# Thing_Plus_ESP32_C6.net
KiCad netlist of a schematic drawn in EAGLE
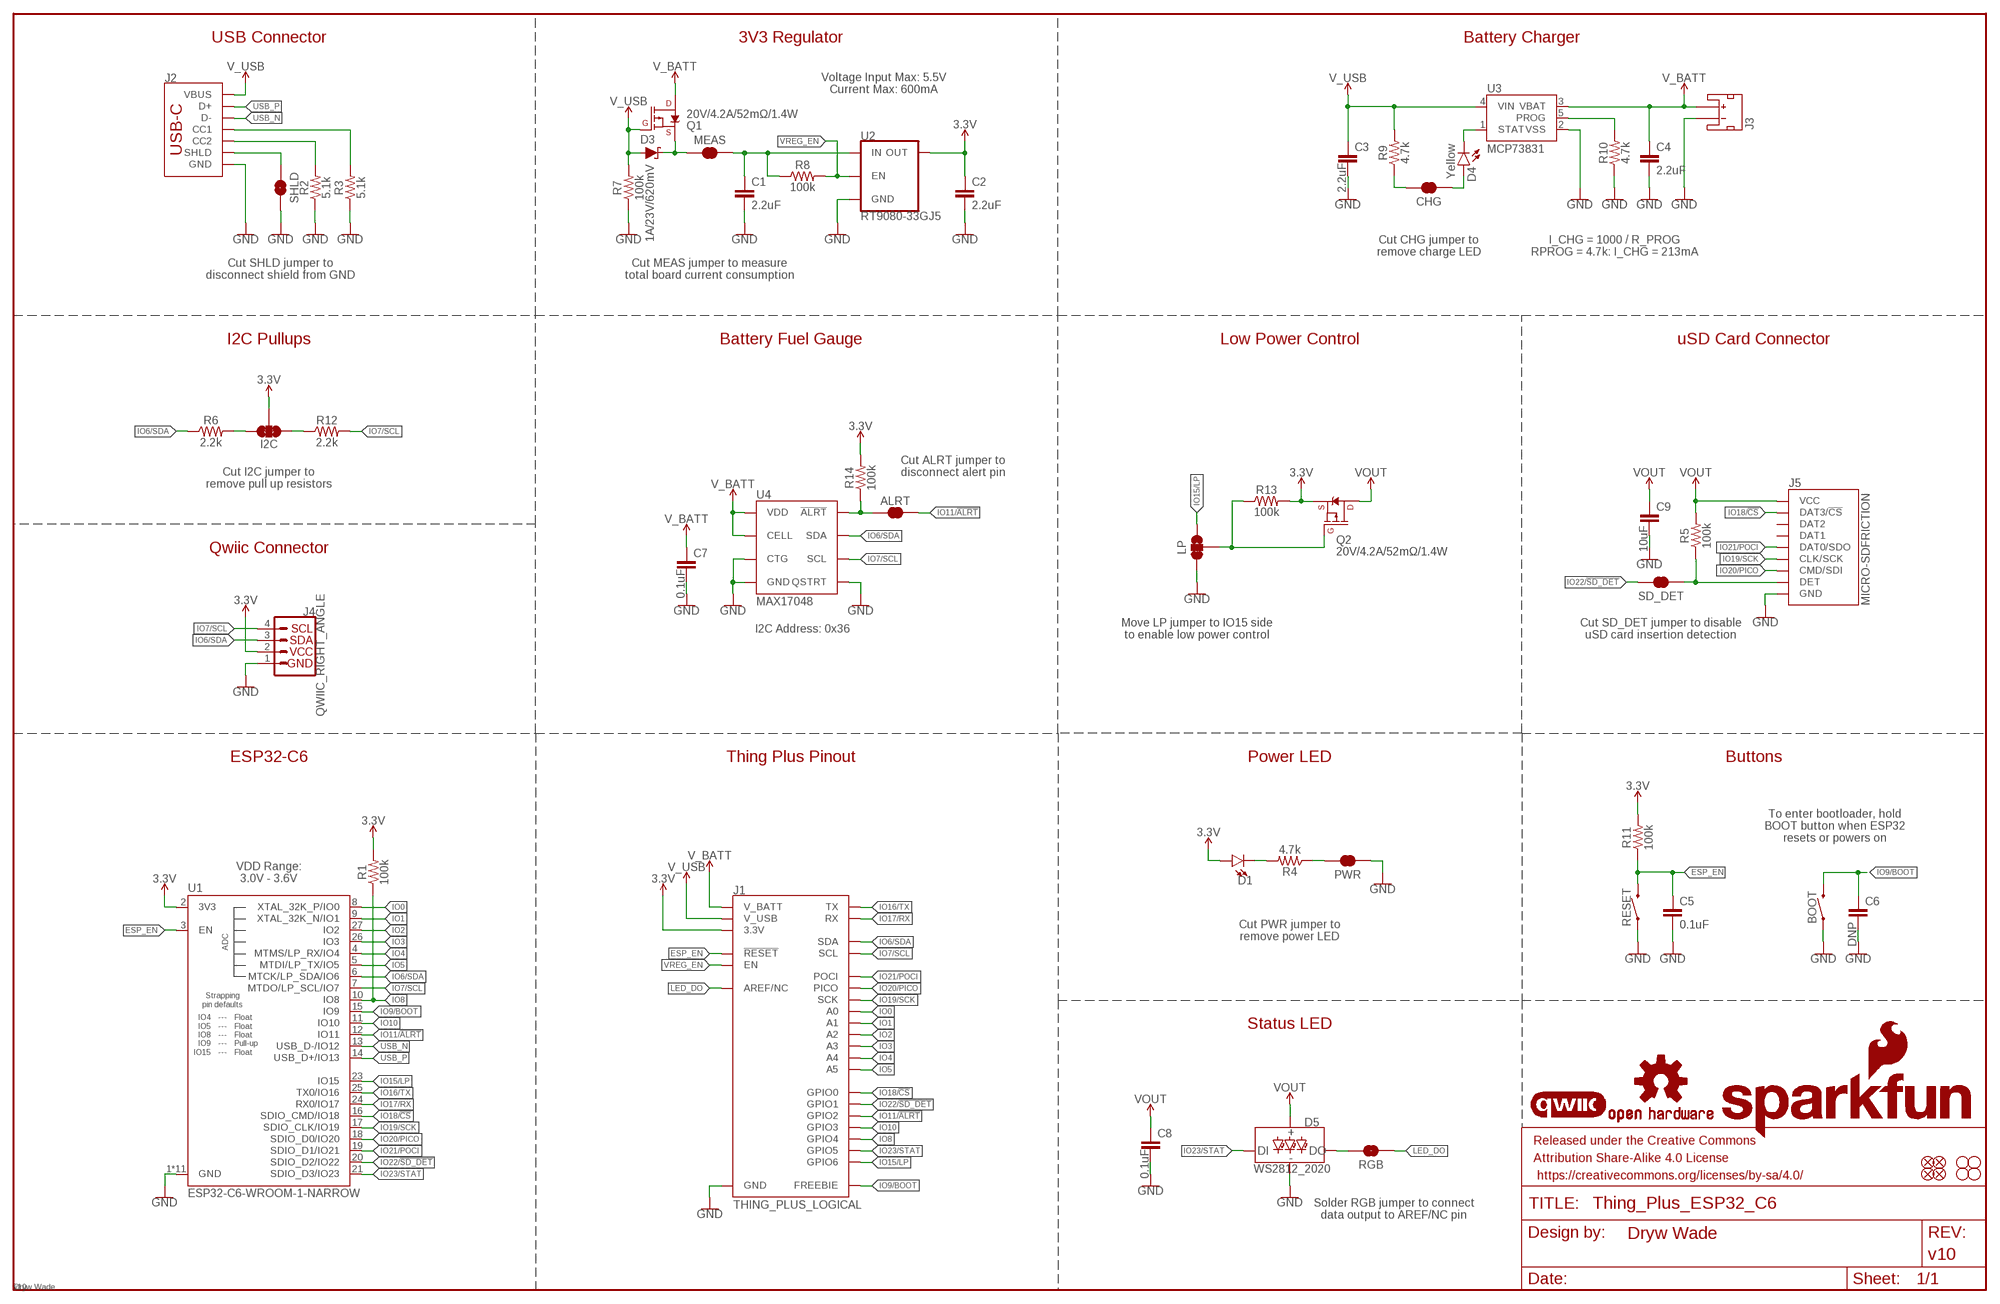
[diagram p0: schematic, sheet 1]

(export (version "E")
  (design (tool "Eeschema 10.0.6"))
  (components
    (comp (ref "ALRT")
      (value "JUMPER-SMT_2_NC_TRACE_SILK")
      (footprint "eagle-import:SMT-JUMPER_2_NC_TRACE_SILK")
      (libsource (lib "eagle-import") (part "JUMPER-SMT_2_NC_TRACE_SILK"))
    )
    (comp (ref "BOOT")
      (value "MOMENTARY-SWITCH-SPST-SMD-4.6X2.8MM")
      (footprint "eagle-import:TACTILE_SWITCH_SMD_4.6X2.8MM")
      (libsource (lib "eagle-import") (part "MOMENTARY-SWITCH-SPST-SMD-4.6X2.8MM"))
    )
    (comp (ref "C1")
      (value "2.2uF")
      (footprint "eagle-import:0603")
      (libsource (lib "eagle-import") (part "2.2UF-0603-10V-20%"))
    )
    (comp (ref "C2")
      (value "2.2uF")
      (footprint "eagle-import:0603")
      (libsource (lib "eagle-import") (part "2.2UF-0603-10V-20%"))
    )
    (comp (ref "C3")
      (value "2.2uF")
      (footprint "eagle-import:0603")
      (libsource (lib "eagle-import") (part "2.2UF-0603-10V-20%"))
    )
    (comp (ref "C4")
      (value "2.2uF")
      (footprint "eagle-import:0603")
      (libsource (lib "eagle-import") (part "2.2UF-0603-10V-20%"))
    )
    (comp (ref "C5")
      (value "0.1uF")
      (footprint "eagle-import:0603")
      (libsource (lib "eagle-import") (part "0.1UF-0603-25V-(+80/-20%)"))
    )
    (comp (ref "C6")
      (value "DNP")
      (footprint "eagle-import:0603")
      (libsource (lib "eagle-import") (part "0.1UF-0603-25V-(+80/-20%)"))
    )
    (comp (ref "C7")
      (value "0.1uF")
      (footprint "eagle-import:0603")
      (libsource (lib "eagle-import") (part "0.1UF-0603-25V-(+80/-20%)"))
    )
    (comp (ref "C8")
      (value "0.1uF")
      (footprint "eagle-import:0603")
      (libsource (lib "eagle-import") (part "0.1UF-0603-25V-(+80/-20%)"))
    )
    (comp (ref "C9")
      (value "10uF")
      (footprint "eagle-import:0603")
      (libsource (lib "eagle-import") (part "10UF-0603-6.3V-20%"))
    )
    (comp (ref "CHG")
      (value "JUMPER-SMT_2_NC_TRACE_SILK")
      (footprint "eagle-import:SMT-JUMPER_2_NC_TRACE_SILK")
      (libsource (lib "eagle-import") (part "JUMPER-SMT_2_NC_TRACE_SILK"))
    )
    (comp (ref "D1")
      (value "LED-RED_0603-KB")
      (footprint "eagle-import:LED-0603")
      (libsource (lib "eagle-import") (part "LED-RED_0603-KB"))
    )
    (comp (ref "D3")
      (value "1A/23V/620mV")
      (footprint "eagle-import:SOD-323")
      (libsource (lib "eagle-import") (part "DIODE-SCHOTTKY-BAT20J"))
    )
    (comp (ref "D4")
      (value "Yellow")
      (footprint "eagle-import:LED-0603")
      (libsource (lib "eagle-import") (part "LED-YELLOW0603"))
    )
    (comp (ref "D5")
      (value "WS2812_2020")
      (footprint "eagle-import:WS2812-2020")
      (libsource (lib "eagle-import") (part "WS2812_2020"))
    )
    (comp (ref "FD1")
      (value "FIDUCIALUFIDUCIAL")
      (footprint "eagle-import:FIDUCIAL-MICRO")
      (libsource (lib "eagle-import") (part "FIDUCIALUFIDUCIAL"))
    )
    (comp (ref "FD2")
      (value "FIDUCIALUFIDUCIAL")
      (footprint "eagle-import:FIDUCIAL-MICRO")
      (libsource (lib "eagle-import") (part "FIDUCIALUFIDUCIAL"))
    )
    (comp (ref "FD3")
      (value "FIDUCIALUFIDUCIAL")
      (footprint "eagle-import:FIDUCIAL-MICRO")
      (libsource (lib "eagle-import") (part "FIDUCIALUFIDUCIAL"))
    )
    (comp (ref "FD4")
      (value "FIDUCIALUFIDUCIAL")
      (footprint "eagle-import:FIDUCIAL-MICRO")
      (libsource (lib "eagle-import") (part "FIDUCIALUFIDUCIAL"))
    )
    (comp (ref "FRAME1")
      (value "FRAME-LEDGER")
      (footprint "eagle-import:CREATIVE_COMMONS")
      (fields (field (name "DESIGNER") "Dryw Wade") (field (name "REV") "v10"))
      (libsource (lib "eagle-import") (part "FRAME-LEDGER"))
    )
    (comp (ref "H1")
      (value "STAND-OFF")
      (footprint "eagle-import:STAND-OFF")
      (libsource (lib "eagle-import") (part "STAND-OFF"))
    )
    (comp (ref "H2")
      (value "STAND-OFF")
      (footprint "eagle-import:STAND-OFF")
      (libsource (lib "eagle-import") (part "STAND-OFF"))
    )
    (comp (ref "H3")
      (value "STAND-OFF")
      (footprint "eagle-import:STAND-OFF")
      (libsource (lib "eagle-import") (part "STAND-OFF"))
    )
    (comp (ref "H4")
      (value "STAND-OFF")
      (footprint "eagle-import:STAND-OFF")
      (libsource (lib "eagle-import") (part "STAND-OFF"))
    )
    (comp (ref "I2C")
      (value "JUMPER-SMT_3_2-NC_TRACE_SILK")
      (footprint "eagle-import:SMT-JUMPER_3_2-NC_TRACE_SILK")
      (libsource (lib "eagle-import") (part "JUMPER-SMT_3_2-NC_TRACE_SILK"))
    )
    (comp (ref "J1")
      (value "THING_PLUS_LOGICAL")
      (footprint "eagle-import:THING_PLUS")
      (libsource (lib "eagle-import") (part "THING_PLUS_LOGICAL"))
    )
    (comp (ref "J2")
      (value "USB_C_4-LAYER_PADS")
      (footprint "eagle-import:USB-C-16P_4LAYER-PADS")
      (libsource (lib "eagle-import") (part "USB_C_4-LAYER_PADS"))
    )
    (comp (ref "J3")
      (value "JST_2MM_MALE")
      (footprint "eagle-import:JST-2-SMD")
      (libsource (lib "eagle-import") (part "JST_2MM_MALE"))
    )
    (comp (ref "J4")
      (value "QWIIC_RIGHT_ANGLE")
      (footprint "eagle-import:JST04_1MM_RA")
      (libsource (lib "eagle-import") (part "QWIIC_CONNECTORJS-1MM"))
    )
    (comp (ref "J5")
      (value "MICRO-SDFRICTION")
      (footprint "eagle-import:MICROSD_TINY")
      (libsource (lib "eagle-import") (part "MICRO-SDFRICTION"))
    )
    (comp (ref "LOGO1")
      (value "SFE_LOGO_NAME_FLAME.1_INCH")
      (footprint "eagle-import:SFE_LOGO_NAME_FLAME_.1")
      (libsource (lib "eagle-import") (part "SFE_LOGO_NAME_FLAME.1_INCH"))
    )
    (comp (ref "LOGO2")
      (value "QWIIC_LOGO_4MM")
      (footprint "eagle-import:QWIIC_4MM")
      (libsource (lib "eagle-import") (part "QWIIC_LOGO_4MM"))
    )
    (comp (ref "LOGO3")
      (value "OSHW-LOGOM")
      (footprint "eagle-import:OSHW-LOGO-M")
      (libsource (lib "eagle-import") (part "OSHW-LOGOM"))
    )
    (comp (ref "LP")
      (value "JUMPER-SMT_3_1-NC_TRACE_SILK")
      (footprint "eagle-import:SMT-JUMPER_3_1-NC_TRACE_SILK")
      (libsource (lib "eagle-import") (part "JUMPER-SMT_3_1-NC_TRACE_SILK"))
    )
    (comp (ref "MEAS")
      (value "JUMPER-COMBO_2_NC_TRACE")
      (footprint "eagle-import:COMBO-JUMPER_2_NC_TRACE")
      (libsource (lib "eagle-import") (part "JUMPER-COMBO_2_NC_TRACE"))
    )
    (comp (ref "PWR")
      (value "JUMPER-SMT_2_NC_TRACE_SILK")
      (footprint "eagle-import:SMT-JUMPER_2_NC_TRACE_SILK")
      (libsource (lib "eagle-import") (part "JUMPER-SMT_2_NC_TRACE_SILK"))
    )
    (comp (ref "Q1")
      (value "20V/4.2A/52mΩ/1.4W")
      (footprint "eagle-import:SOT23-3")
      (libsource (lib "eagle-import") (part "MOSFET_PCH-DMG2305UX-7"))
    )
    (comp (ref "Q2")
      (value "20V/4.2A/52mΩ/1.4W")
      (footprint "eagle-import:SOT23-3")
      (libsource (lib "eagle-import") (part "MOSFET_PCH-DMG2305UX-7"))
    )
    (comp (ref "R1")
      (value "100k")
      (footprint "eagle-import:0603")
      (libsource (lib "eagle-import") (part "100KOHM-0603-1/10W-1%"))
    )
    (comp (ref "R2")
      (value "5.1k")
      (footprint "eagle-import:0603")
      (libsource (lib "eagle-import") (part "5.1KOHM5.1KOHM-0603-1/10W-1%"))
    )
    (comp (ref "R3")
      (value "5.1k")
      (footprint "eagle-import:0603")
      (libsource (lib "eagle-import") (part "5.1KOHM5.1KOHM-0603-1/10W-1%"))
    )
    (comp (ref "R4")
      (value "4.7k")
      (footprint "eagle-import:0603")
      (libsource (lib "eagle-import") (part "4.7KOHM-0603-1/10W-1%"))
    )
    (comp (ref "R5")
      (value "100k")
      (footprint "eagle-import:0603")
      (libsource (lib "eagle-import") (part "100KOHM-0603-1/10W-1%"))
    )
    (comp (ref "R6")
      (value "2.2k")
      (footprint "eagle-import:0603")
      (libsource (lib "eagle-import") (part "2.2KOHM-0603-1/10W-1%"))
    )
    (comp (ref "R7")
      (value "100k")
      (footprint "eagle-import:0603")
      (libsource (lib "eagle-import") (part "100KOHM-0603-1/10W-1%"))
    )
    (comp (ref "R8")
      (value "100k")
      (footprint "eagle-import:0603")
      (libsource (lib "eagle-import") (part "100KOHM-0603-1/10W-1%"))
    )
    (comp (ref "R9")
      (value "4.7k")
      (footprint "eagle-import:0603")
      (libsource (lib "eagle-import") (part "4.7KOHM-0603-1/10W-1%"))
    )
    (comp (ref "R10")
      (value "4.7k")
      (footprint "eagle-import:0603")
      (libsource (lib "eagle-import") (part "4.7KOHM-0603-1/10W-1%"))
    )
    (comp (ref "R11")
      (value "100k")
      (footprint "eagle-import:0603")
      (libsource (lib "eagle-import") (part "100KOHM-0603-1/10W-1%"))
    )
    (comp (ref "R12")
      (value "2.2k")
      (footprint "eagle-import:0603")
      (libsource (lib "eagle-import") (part "2.2KOHM-0603-1/10W-1%"))
    )
    (comp (ref "R13")
      (value "100k")
      (footprint "eagle-import:0603")
      (libsource (lib "eagle-import") (part "100KOHM-0603-1/10W-1%"))
    )
    (comp (ref "R14")
      (value "100k")
      (footprint "eagle-import:0603")
      (libsource (lib "eagle-import") (part "100KOHM-0603-1/10W-1%"))
    )
    (comp (ref "RESET")
      (value "MOMENTARY-SWITCH-SPST-SMD-4.6X2.8MM")
      (footprint "eagle-import:TACTILE_SWITCH_SMD_4.6X2.8MM")
      (libsource (lib "eagle-import") (part "MOMENTARY-SWITCH-SPST-SMD-4.6X2.8MM"))
    )
    (comp (ref "RGB")
      (value "JUMPER-SMT_2_NO_SILK")
      (footprint "eagle-import:SMT-JUMPER_2_NO_SILK")
      (libsource (lib "eagle-import") (part "JUMPER-SMT_2_NO_SILK"))
    )
    (comp (ref "SD_DET")
      (value "JUMPER-SMT_2_NC_TRACE_SILK")
      (footprint "eagle-import:SMT-JUMPER_2_NC_TRACE_SILK")
      (libsource (lib "eagle-import") (part "JUMPER-SMT_2_NC_TRACE_SILK"))
    )
    (comp (ref "SHLD")
      (value "JUMPER-SMT_2_NC_TRACE_SILK")
      (footprint "eagle-import:SMT-JUMPER_2_NC_TRACE_SILK")
      (libsource (lib "eagle-import") (part "JUMPER-SMT_2_NC_TRACE_SILK"))
    )
    (comp (ref "U1")
      (value "ESP32-C6-WROOM-1-NARROW")
      (footprint "eagle-import:ESP32-C6-WROOM-1-NARROW")
      (libsource (lib "eagle-import") (part "ESP32-C6-WROOM-1-NARROW"))
    )
    (comp (ref "U2")
      (value "RT9080-33GJ5")
      (footprint "eagle-import:SOT23-5")
      (libsource (lib "eagle-import") (part "V_REG_RT9080"))
    )
    (comp (ref "U3")
      (value "MCP73831")
      (footprint "eagle-import:SOT23-5")
      (libsource (lib "eagle-import") (part "MCP73831"))
    )
    (comp (ref "U4")
      (value "MAX17048")
      (footprint "eagle-import:DFN-8")
      (libsource (lib "eagle-import") (part "MAX17048DFN8"))
    )
  )
  (nets
    (net (code "1") (name "/IO11{slash}~{ALRT}") (class "Default")
      (node (ref "ALRT") (pin "2") (pinfunction "2_2") (pintype "passive"))
      (node (ref "J1") (pin "7") (pinfunction "GPIO2_7") (pintype "bidirectional"))
      (node (ref "U1") (pin "12") (pinfunction "IO11_12") (pintype "bidirectional"))
    )
    (net (code "2") (name "/IO18{slash}~{CS}") (class "Default")
      (node (ref "J1") (pin "9") (pinfunction "GPIO0_9") (pintype "bidirectional"))
      (node (ref "J5") (pin "2") (pinfunction "DAT3/~{CS}_2") (pintype "bidirectional"))
      (node (ref "U1") (pin "16") (pinfunction "SDIO_CMD/IO18_16") (pintype "bidirectional"))
    )
    (net (code "3") (name "/IO22{slash}~{SD_DET}") (class "Default")
      (node (ref "J1") (pin "8") (pinfunction "GPIO1_8") (pintype "bidirectional"))
      (node (ref "SD_DET") (pin "2") (pinfunction "2_2") (pintype "passive"))
      (node (ref "U1") (pin "20") (pinfunction "SDIO_D2/IO22_20") (pintype "bidirectional"))
    )
    (net (code "4") (name "3.3V") (class "Default")
      (node (ref "C2") (pin "1") (pinfunction "1_1") (pintype "passive"))
      (node (ref "D1") (pin "A") (pinfunction "A_A") (pintype "passive"))
      (node (ref "I2C") (pin "2") (pinfunction "2_2") (pintype "passive"))
      (node (ref "J1") (pin "27") (pinfunction "3.3V_27") (pintype "bidirectional"))
      (node (ref "J4") (pin "2") (pinfunction "2_2") (pintype "power_in"))
      (node (ref "Q2") (pin "2") (pinfunction "S_2") (pintype "bidirectional"))
      (node (ref "R1") (pin "2") (pinfunction "2_2") (pintype "passive"))
      (node (ref "R11") (pin "2") (pinfunction "2_2") (pintype "passive"))
      (node (ref "R13") (pin "2") (pinfunction "2_2") (pintype "passive"))
      (node (ref "R14") (pin "2") (pinfunction "2_2") (pintype "passive"))
      (node (ref "U1") (pin "2") (pinfunction "3V3_2") (pintype "bidirectional"))
      (node (ref "U2") (pin "5") (pinfunction "OUT_5") (pintype "passive"))
    )
    (net (code "5") (name "ESP_EN") (class "Default")
      (node (ref "C5") (pin "1") (pinfunction "1_1") (pintype "passive"))
      (node (ref "J1") (pin "28") (pinfunction "~{RESET}_28") (pintype "bidirectional"))
      (node (ref "R11") (pin "1") (pinfunction "1_1") (pintype "passive"))
      (node (ref "RESET") (pin "3") (pinfunction "2_3") (pintype "passive"))
      (node (ref "RESET") (pin "4") (pinfunction "2_4") (pintype "passive"))
      (node (ref "U1") (pin "3") (pinfunction "EN_3") (pintype "bidirectional"))
    )
    (net (code "6") (name "GND") (class "Default")
      (node (ref "BOOT") (pin "1") (pinfunction "1_1") (pintype "passive"))
      (node (ref "BOOT") (pin "2") (pinfunction "1_2") (pintype "passive"))
      (node (ref "C1") (pin "2") (pinfunction "2_2") (pintype "passive"))
      (node (ref "C2") (pin "2") (pinfunction "2_2") (pintype "passive"))
      (node (ref "C3") (pin "2") (pinfunction "2_2") (pintype "passive"))
      (node (ref "C4") (pin "2") (pinfunction "2_2") (pintype "passive"))
      (node (ref "C5") (pin "2") (pinfunction "2_2") (pintype "passive"))
      (node (ref "C6") (pin "2") (pinfunction "2_2") (pintype "passive"))
      (node (ref "C7") (pin "2") (pinfunction "2_2") (pintype "passive"))
      (node (ref "C8") (pin "2") (pinfunction "2_2") (pintype "passive"))
      (node (ref "C9") (pin "2") (pinfunction "2_2") (pintype "passive"))
      (node (ref "D5") (pin "GND") (pinfunction "GND_GND") (pintype "bidirectional"))
      (node (ref "J1") (pin "25") (pinfunction "GND_25") (pintype "bidirectional"))
      (node (ref "J2") (pin "GND") (pinfunction "GND_GND") (pintype "bidirectional"))
      (node (ref "J2") (pin "GND2") (pinfunction "GND_GND2") (pintype "bidirectional"))
      (node (ref "J3") (pin "1") (pinfunction "-_1") (pintype "bidirectional"))
      (node (ref "J4") (pin "1") (pinfunction "1_1") (pintype "power_in"))
      (node (ref "J5") (pin "6") (pinfunction "GND_6") (pintype "bidirectional"))
      (node (ref "J5") (pin "GND1") (pinfunction "GND_GND1") (pintype "bidirectional"))
      (node (ref "J5") (pin "GND2") (pinfunction "GND_GND2") (pintype "bidirectional"))
      (node (ref "J5") (pin "GND3") (pinfunction "GND_GND3") (pintype "bidirectional"))
      (node (ref "J5") (pin "GND4") (pinfunction "GND_GND4") (pintype "bidirectional"))
      (node (ref "J5") (pin "GND5") (pinfunction "GND_GND5") (pintype "bidirectional"))
      (node (ref "J5") (pin "GND6") (pinfunction "GND_GND6") (pintype "bidirectional"))
      (node (ref "LP") (pin "3") (pinfunction "3_3") (pintype "passive"))
      (node (ref "PWR") (pin "1") (pinfunction "1_1") (pintype "passive"))
      (node (ref "R10") (pin "1") (pinfunction "1_1") (pintype "passive"))
      (node (ref "R2") (pin "1") (pinfunction "1_1") (pintype "passive"))
      (node (ref "R3") (pin "1") (pinfunction "1_1") (pintype "passive"))
      (node (ref "R7") (pin "1") (pinfunction "1_1") (pintype "passive"))
      (node (ref "RESET") (pin "1") (pinfunction "1_1") (pintype "passive"))
      (node (ref "RESET") (pin "2") (pinfunction "1_2") (pintype "passive"))
      (node (ref "SHLD") (pin "2") (pinfunction "2_2") (pintype "passive"))
      (node (ref "U1") (pin "1") (pinfunction "GND_1") (pintype "bidirectional"))
      (node (ref "U1") (pin "28") (pinfunction "GND_28") (pintype "bidirectional"))
      (node (ref "U1") (pin "29") (pinfunction "GND_29") (pintype "bidirectional"))
      (node (ref "U1") (pin "30") (pinfunction "GND_30") (pintype "bidirectional"))
      (node (ref "U1") (pin "31") (pinfunction "GND_31") (pintype "bidirectional"))
      (node (ref "U1") (pin "32") (pinfunction "GND_32") (pintype "bidirectional"))
      (node (ref "U1") (pin "33") (pinfunction "GND_33") (pintype "bidirectional"))
      (node (ref "U1") (pin "34") (pinfunction "GND_34") (pintype "bidirectional"))
      (node (ref "U1") (pin "35") (pinfunction "GND_35") (pintype "bidirectional"))
      (node (ref "U1") (pin "36") (pinfunction "GND_36") (pintype "bidirectional"))
      (node (ref "U1") (pin "37") (pinfunction "GND_37") (pintype "bidirectional"))
      (node (ref "U2") (pin "2") (pinfunction "GND_2") (pintype "input"))
      (node (ref "U3") (pin "2") (pinfunction "VSS_2") (pintype "power_in"))
      (node (ref "U4") (pin "1") (pinfunction "CTG_1") (pintype "input"))
      (node (ref "U4") (pin "4") (pinfunction "GND_4") (pintype "bidirectional"))
      (node (ref "U4") (pin "6") (pinfunction "QSTRT_6") (pintype "bidirectional"))
      (node (ref "U4") (pin "9") (pinfunction "GND_9") (pintype "bidirectional"))
    )
    (net (code "7") (name "IO0") (class "Default")
      (node (ref "J1") (pin "24") (pinfunction "A0_24") (pintype "bidirectional"))
      (node (ref "U1") (pin "8") (pinfunction "XTAL_32K_P/IO0_8") (pintype "bidirectional"))
    )
    (net (code "8") (name "IO1") (class "Default")
      (node (ref "J1") (pin "23") (pinfunction "A1_23") (pintype "bidirectional"))
      (node (ref "U1") (pin "9") (pinfunction "XTAL_32K_N/IO1_9") (pintype "bidirectional"))
    )
    (net (code "9") (name "IO2") (class "Default")
      (node (ref "J1") (pin "22") (pinfunction "A2_22") (pintype "bidirectional"))
      (node (ref "U1") (pin "27") (pinfunction "IO2_27") (pintype "bidirectional"))
    )
    (net (code "10") (name "IO3") (class "Default")
      (node (ref "J1") (pin "21") (pinfunction "A3_21") (pintype "bidirectional"))
      (node (ref "U1") (pin "26") (pinfunction "IO3_26") (pintype "bidirectional"))
    )
    (net (code "11") (name "IO4") (class "Default")
      (node (ref "J1") (pin "20") (pinfunction "A4_20") (pintype "bidirectional"))
      (node (ref "U1") (pin "4") (pinfunction "MTMS/LP_RX/IO4_4") (pintype "bidirectional"))
    )
    (net (code "12") (name "IO5") (class "Default")
      (node (ref "J1") (pin "19") (pinfunction "A5_19") (pintype "bidirectional"))
      (node (ref "U1") (pin "5") (pinfunction "MTDI/LP_TX/IO5_5") (pintype "bidirectional"))
    )
    (net (code "13") (name "IO6{slash}SDA") (class "Default")
      (node (ref "J1") (pin "1") (pinfunction "SDA_1") (pintype "bidirectional"))
      (node (ref "J4") (pin "3") (pinfunction "3_3") (pintype "passive"))
      (node (ref "R6") (pin "1") (pinfunction "1_1") (pintype "passive"))
      (node (ref "U1") (pin "6") (pinfunction "MTCK/LP_SDA/IO6_6") (pintype "bidirectional"))
      (node (ref "U4") (pin "8") (pinfunction "SDA_8") (pintype "input"))
    )
    (net (code "14") (name "IO7{slash}SCL") (class "Default")
      (node (ref "J1") (pin "2") (pinfunction "SCL_2") (pintype "bidirectional"))
      (node (ref "J4") (pin "4") (pinfunction "4_4") (pintype "passive"))
      (node (ref "R12") (pin "2") (pinfunction "2_2") (pintype "passive"))
      (node (ref "U1") (pin "7") (pinfunction "MTDO/LP_SCL/IO7_7") (pintype "bidirectional"))
      (node (ref "U4") (pin "7") (pinfunction "SCL_7") (pintype "output"))
    )
    (net (code "15") (name "IO8") (class "Default")
      (node (ref "J1") (pin "5") (pinfunction "GPIO4_5") (pintype "bidirectional"))
      (node (ref "R1") (pin "1") (pinfunction "1_1") (pintype "passive"))
      (node (ref "U1") (pin "10") (pinfunction "IO8_10") (pintype "bidirectional"))
    )
    (net (code "16") (name "IO9{slash}BOOT") (class "Default")
      (node (ref "BOOT") (pin "3") (pinfunction "2_3") (pintype "passive"))
      (node (ref "BOOT") (pin "4") (pinfunction "2_4") (pintype "passive"))
      (node (ref "C6") (pin "1") (pinfunction "1_1") (pintype "passive"))
      (node (ref "J1") (pin "13") (pinfunction "FREEBIE_13") (pintype "bidirectional"))
      (node (ref "U1") (pin "15") (pinfunction "IO9_15") (pintype "bidirectional"))
    )
    (net (code "17") (name "IO10") (class "Default")
      (node (ref "J1") (pin "6") (pinfunction "GPIO3_6") (pintype "bidirectional"))
      (node (ref "U1") (pin "11") (pinfunction "IO10_11") (pintype "bidirectional"))
    )
    (net (code "18") (name "IO15{slash}LP") (class "Default")
      (node (ref "J1") (pin "3") (pinfunction "GPIO6_3") (pintype "bidirectional"))
      (node (ref "LP") (pin "1") (pinfunction "1_1") (pintype "passive"))
      (node (ref "U1") (pin "23") (pinfunction "IO15_23") (pintype "bidirectional"))
    )
    (net (code "19") (name "IO16{slash}TX") (class "Default")
      (node (ref "J1") (pin "14") (pinfunction "TX_14") (pintype "bidirectional"))
      (node (ref "U1") (pin "25") (pinfunction "TX0/IO16_25") (pintype "bidirectional"))
    )
    (net (code "20") (name "IO17{slash}RX") (class "Default")
      (node (ref "J1") (pin "15") (pinfunction "RX_15") (pintype "bidirectional"))
      (node (ref "U1") (pin "24") (pinfunction "RX0/IO17_24") (pintype "bidirectional"))
    )
    (net (code "21") (name "IO19{slash}SCK") (class "Default")
      (node (ref "J1") (pin "18") (pinfunction "SCK_18") (pintype "bidirectional"))
      (node (ref "J5") (pin "5") (pinfunction "CLK/SCK_5") (pintype "bidirectional"))
      (node (ref "U1") (pin "17") (pinfunction "SDIO_CLK/IO19_17") (pintype "bidirectional"))
    )
    (net (code "22") (name "IO20{slash}PICO") (class "Default")
      (node (ref "J1") (pin "17") (pinfunction "PICO_17") (pintype "bidirectional"))
      (node (ref "J5") (pin "3") (pinfunction "CMD/SDI_3") (pintype "bidirectional"))
      (node (ref "U1") (pin "18") (pinfunction "SDIO_D0/IO20_18") (pintype "bidirectional"))
    )
    (net (code "23") (name "IO21{slash}POCI") (class "Default")
      (node (ref "J1") (pin "16") (pinfunction "POCI_16") (pintype "bidirectional"))
      (node (ref "J5") (pin "7") (pinfunction "DAT0/SDO_7") (pintype "bidirectional"))
      (node (ref "U1") (pin "19") (pinfunction "SDIO_D1/IO21_19") (pintype "bidirectional"))
    )
    (net (code "24") (name "IO23{slash}STAT") (class "Default")
      (node (ref "D5") (pin "DI") (pinfunction "DI_DI") (pintype "bidirectional"))
      (node (ref "J1") (pin "4") (pinfunction "GPIO5_4") (pintype "bidirectional"))
      (node (ref "U1") (pin "21") (pinfunction "SDIO_D3/IO23_21") (pintype "bidirectional"))
    )
    (net (code "25") (name "LED_DO") (class "Default")
      (node (ref "J1") (pin "26") (pinfunction "AREF/NC_26") (pintype "bidirectional"))
      (node (ref "RGB") (pin "1") (pinfunction "1_1") (pintype "passive"))
    )
    (net (code "26") (name "Net-(CHG-Pad1)") (class "Default")
      (node (ref "CHG") (pin "1") (pinfunction "1_1") (pintype "passive"))
      (node (ref "D4") (pin "A") (pinfunction "A_A") (pintype "passive"))
    )
    (net (code "27") (name "Net-(CHG-Pad2)") (class "Default")
      (node (ref "CHG") (pin "2") (pinfunction "2_2") (pintype "passive"))
      (node (ref "R9") (pin "1") (pinfunction "1_1") (pintype "passive"))
    )
    (net (code "28") (name "Net-(D1-PadC)") (class "Default")
      (node (ref "D1") (pin "C") (pinfunction "C_C") (pintype "passive"))
      (node (ref "R4") (pin "2") (pinfunction "2_2") (pintype "passive"))
    )
    (net (code "29") (name "Net-(D5-PadDO)") (class "Default")
      (node (ref "D5") (pin "DO") (pinfunction "DO_DO") (pintype "bidirectional"))
      (node (ref "RGB") (pin "2") (pinfunction "2_2") (pintype "passive"))
    )
    (net (code "30") (name "Net-(I2C-Pad1)") (class "Default")
      (node (ref "I2C") (pin "1") (pinfunction "1_1") (pintype "passive"))
      (node (ref "R12") (pin "1") (pinfunction "1_1") (pintype "passive"))
    )
    (net (code "31") (name "Net-(I2C-Pad3)") (class "Default")
      (node (ref "I2C") (pin "3") (pinfunction "3_3") (pintype "passive"))
      (node (ref "R6") (pin "2") (pinfunction "2_2") (pintype "passive"))
    )
    (net (code "32") (name "Net-(J2-CC1)") (class "Default")
      (node (ref "J2") (pin "A5") (pinfunction "CC1_A5") (pintype "bidirectional"))
      (node (ref "R3") (pin "2") (pinfunction "2_2") (pintype "passive"))
    )
    (net (code "33") (name "Net-(J2-CC2)") (class "Default")
      (node (ref "J2") (pin "B5") (pinfunction "CC2_B5") (pintype "bidirectional"))
      (node (ref "R2") (pin "2") (pinfunction "2_2") (pintype "passive"))
    )
    (net (code "34") (name "Net-(J2-SHLD-PadSHLD1)") (class "Default")
      (node (ref "J2") (pin "SHLD1") (pinfunction "SHLD_SHLD1") (pintype "bidirectional"))
      (node (ref "J2") (pin "SHLD2") (pinfunction "SHLD_SHLD2") (pintype "bidirectional"))
      (node (ref "J2") (pin "SHLD3") (pinfunction "SHLD_SHLD3") (pintype "bidirectional"))
      (node (ref "J2") (pin "SHLD4") (pinfunction "SHLD_SHLD4") (pintype "bidirectional"))
      (node (ref "SHLD") (pin "1") (pinfunction "1_1") (pintype "passive"))
    )
    (net (code "35") (name "Net-(J5-DET)") (class "Default")
      (node (ref "J5") (pin "9") (pinfunction "DET_9") (pintype "bidirectional"))
      (node (ref "R5") (pin "1") (pinfunction "1_1") (pintype "passive"))
      (node (ref "SD_DET") (pin "1") (pinfunction "1_1") (pintype "passive"))
    )
    (net (code "36") (name "Net-(PWR-Pad2)") (class "Default")
      (node (ref "PWR") (pin "2") (pinfunction "2_2") (pintype "passive"))
      (node (ref "R4") (pin "1") (pinfunction "1_1") (pintype "passive"))
    )
    (net (code "37") (name "Net-(Q1-S)") (class "Default")
      (node (ref "D3") (pin "C") (pinfunction "C_C") (pintype "passive"))
      (node (ref "MEAS") (pin "1") (pinfunction "1_1") (pintype "passive"))
      (node (ref "MEAS") (pin "3") (pinfunction "1_3") (pintype "passive"))
      (node (ref "Q1") (pin "2") (pinfunction "S_2") (pintype "bidirectional"))
    )
    (net (code "38") (name "Net-(Q2-G)") (class "Default")
      (node (ref "LP") (pin "2") (pinfunction "2_2") (pintype "passive"))
      (node (ref "Q2") (pin "1") (pinfunction "G_1") (pintype "bidirectional"))
      (node (ref "R13") (pin "1") (pinfunction "1_1") (pintype "passive"))
    )
    (net (code "39") (name "Net-(U2-IN)") (class "Default")
      (node (ref "C1") (pin "1") (pinfunction "1_1") (pintype "passive"))
      (node (ref "MEAS") (pin "2") (pinfunction "2_2") (pintype "passive"))
      (node (ref "MEAS") (pin "4") (pinfunction "2_4") (pintype "passive"))
      (node (ref "R8") (pin "1") (pinfunction "1_1") (pintype "passive"))
      (node (ref "U2") (pin "1") (pinfunction "IN_1") (pintype "input"))
    )
    (net (code "40") (name "Net-(U3-PROG)") (class "Default")
      (node (ref "R10") (pin "2") (pinfunction "2_2") (pintype "passive"))
      (node (ref "U3") (pin "5") (pinfunction "PROG_5") (pintype "input"))
    )
    (net (code "41") (name "Net-(U3-STAT)") (class "Default")
      (node (ref "D4") (pin "C") (pinfunction "C_C") (pintype "passive"))
      (node (ref "U3") (pin "1") (pinfunction "STAT_1") (pintype "output"))
    )
    (net (code "42") (name "Net-(U4-~{ALRT})") (class "Default")
      (node (ref "ALRT") (pin "1") (pinfunction "1_1") (pintype "passive"))
      (node (ref "R14") (pin "1") (pinfunction "1_1") (pintype "passive"))
      (node (ref "U4") (pin "5") (pinfunction "~{ALRT}_5") (pintype "bidirectional"))
    )
    (net (code "43") (name "USB_N") (class "Default")
      (node (ref "J2") (pin "A7") (pinfunction "D-_A7") (pintype "bidirectional"))
      (node (ref "J2") (pin "B7") (pinfunction "D-_B7") (pintype "bidirectional"))
      (node (ref "U1") (pin "13") (pinfunction "USB_D-/IO12_13") (pintype "bidirectional"))
    )
    (net (code "44") (name "USB_P") (class "Default")
      (node (ref "J2") (pin "A6") (pinfunction "D+_A6") (pintype "bidirectional"))
      (node (ref "J2") (pin "B6") (pinfunction "D+_B6") (pintype "bidirectional"))
      (node (ref "U1") (pin "14") (pinfunction "USB_D+/IO13_14") (pintype "bidirectional"))
    )
    (net (code "45") (name "VOUT") (class "Default")
      (node (ref "C8") (pin "1") (pinfunction "1_1") (pintype "passive"))
      (node (ref "C9") (pin "1") (pinfunction "1_1") (pintype "passive"))
      (node (ref "D5") (pin "VCC") (pinfunction "VCC_VCC") (pintype "bidirectional"))
      (node (ref "J5") (pin "4") (pinfunction "VCC_4") (pintype "bidirectional"))
      (node (ref "Q2") (pin "3") (pinfunction "D_3") (pintype "bidirectional"))
      (node (ref "R5") (pin "2") (pinfunction "2_2") (pintype "passive"))
    )
    (net (code "46") (name "VREG_EN") (class "Default")
      (node (ref "J1") (pin "11") (pinfunction "EN_11") (pintype "bidirectional"))
      (node (ref "R8") (pin "2") (pinfunction "2_2") (pintype "passive"))
      (node (ref "U2") (pin "3") (pinfunction "EN_3") (pintype "input"))
    )
    (net (code "47") (name "V_BATT") (class "Default")
      (node (ref "C4") (pin "1") (pinfunction "1_1") (pintype "passive"))
      (node (ref "C7") (pin "1") (pinfunction "1_1") (pintype "passive"))
      (node (ref "J1") (pin "12") (pinfunction "V_BATT_12") (pintype "bidirectional"))
      (node (ref "J3") (pin "2") (pinfunction "+_2") (pintype "bidirectional"))
      (node (ref "Q1") (pin "3") (pinfunction "D_3") (pintype "bidirectional"))
      (node (ref "U3") (pin "3") (pinfunction "VBAT_3") (pintype "power_in"))
      (node (ref "U4") (pin "2") (pinfunction "CELL_2") (pintype "input"))
      (node (ref "U4") (pin "3") (pinfunction "VDD_3") (pintype "bidirectional"))
    )
    (net (code "48") (name "V_USB") (class "Default")
      (node (ref "C3") (pin "1") (pinfunction "1_1") (pintype "passive"))
      (node (ref "D3") (pin "A") (pinfunction "A_A") (pintype "passive"))
      (node (ref "J1") (pin "10") (pinfunction "V_USB_10") (pintype "bidirectional"))
      (node (ref "J2") (pin "VBUS1") (pinfunction "VBUS_VBUS1") (pintype "bidirectional"))
      (node (ref "J2") (pin "VBUS2") (pinfunction "VBUS_VBUS2") (pintype "bidirectional"))
      (node (ref "Q1") (pin "1") (pinfunction "G_1") (pintype "bidirectional"))
      (node (ref "R7") (pin "2") (pinfunction "2_2") (pintype "passive"))
      (node (ref "R9") (pin "2") (pinfunction "2_2") (pintype "passive"))
      (node (ref "U3") (pin "4") (pinfunction "VIN_4") (pintype "power_in"))
    )
    (net (code "49") (name "unconnected-(J3-PAD1-PadNC1)") (class "Default")
      (node (ref "J3") (pin "NC1") (pinfunction "PAD1_NC1") (pintype "bidirectional"))
    )
    (net (code "50") (name "unconnected-(J3-PAD2-PadNC2)") (class "Default")
      (node (ref "J3") (pin "NC2") (pinfunction "PAD2_NC2") (pintype "bidirectional"))
    )
    (net (code "51") (name "unconnected-(J5-DAT1-Pad8)") (class "Default")
      (node (ref "J5") (pin "8") (pinfunction "DAT1_8") (pintype "bidirectional"))
    )
    (net (code "52") (name "unconnected-(J5-DAT2-Pad1)") (class "Default")
      (node (ref "J5") (pin "1") (pinfunction "DAT2_1") (pintype "bidirectional"))
    )
  )
)
